# CRAFT_Negativesupply.net
KiCad netlist of a schematic drawn in Altium Designer
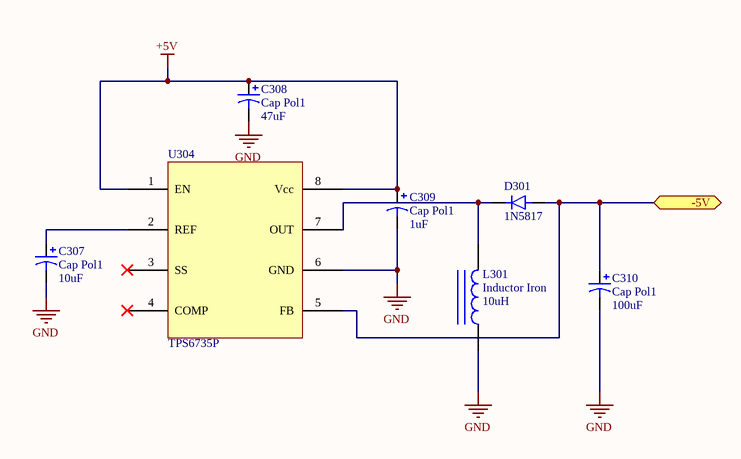
[diagram p0: CRAFT_Negativesupply.SchDoc]

(export (version "E")
  (design (tool "Eeschema 10.0.6"))
  (components
    (comp (ref "C307")
      (value "Cap Pol1")
      (footprint "CAPPRD250W50D630H1120")
      (description "Polarized Capacitor (Radial)")
      (fields (field (name "ALTIUM_VALUE") "10uF") (field (name "PUBLISHER") "Altium Limited"))
      (libsource (lib "Miscellaneous Devices") (part "Cap Pol1"))
    )
    (comp (ref "C308")
      (value "Cap Pol1")
      (footprint "CAPPRD250W50D630H1120")
      (description "Polarized Capacitor (Radial)")
      (fields (field (name "ALTIUM_VALUE") "47uF") (field (name "PUBLISHER") "Altium Limited"))
      (libsource (lib "Miscellaneous Devices") (part "Cap Pol1"))
    )
    (comp (ref "C309")
      (value "Cap Pol1")
      (footprint "CAPPRD250W50D630H1120")
      (description "Polarized Capacitor (Radial)")
      (fields (field (name "ALTIUM_VALUE") "1uF") (field (name "PUBLISHER") "Altium Limited"))
      (libsource (lib "Miscellaneous Devices") (part "Cap Pol1"))
    )
    (comp (ref "C310")
      (value "Cap Pol1")
      (footprint "CAPPRD250W50D630H1120")
      (description "Polarized Capacitor (Radial)")
      (fields (field (name "ALTIUM_VALUE") "100uF") (field (name "PUBLISHER") "Altium Limited"))
      (libsource (lib "Miscellaneous Devices") (part "Cap Pol1"))
    )
    (comp (ref "D301")
      (value "1N5817")
      (footprint "DIOAD1036W78L470D235")
      (description "Diode Schottky 20 V 1A Through Hole DO-41")
      (fields (field (name "MF") "STMicroelectronics"))
      (libsource (lib "1N5817") (part "1N5817"))
    )
    (comp (ref "L301")
      (value "Inductor Iron")
      (footprint "INDRD500W70D900H1220")
      (description "Magnetic-Core Inductor")
      (fields (field (name "ALTIUM_VALUE") "10uH") (field (name "PUBLISHER") "Altium Limited"))
      (libsource (lib "Miscellaneous Devices") (part "Inductor Iron"))
    )
    (comp (ref "U304")
      (value "TPS6735P")
      (footprint "DIP794W45P254L959H508Q8")
      (libsource (lib "CRAFTSchlib") (part "TPS6735P"))
    )
  )
  (nets
    (net (code "1") (name "+5V") (class "Default")
      (node (ref "C308") (pin "1") (pinfunction "1_1") (pintype "passive"))
      (node (ref "C309") (pin "1") (pinfunction "1_1") (pintype "passive"))
      (node (ref "U304") (pin "1") (pinfunction "EN_1") (pintype "passive"))
      (node (ref "U304") (pin "8") (pinfunction "Vcc_8") (pintype "passive"))
    )
    (net (code "2") (name "/-5V") (class "Default")
      (node (ref "C310") (pin "1") (pinfunction "1_1") (pintype "passive"))
      (node (ref "D301") (pin "A") (pinfunction "A_A") (pintype "passive"))
      (node (ref "U304") (pin "5") (pinfunction "FB_5") (pintype "passive"))
    )
    (net (code "3") (name "GND") (class "Default")
      (node (ref "C307") (pin "2") (pinfunction "2_2") (pintype "passive"))
      (node (ref "C308") (pin "2") (pinfunction "2_2") (pintype "passive"))
      (node (ref "C309") (pin "2") (pinfunction "2_2") (pintype "passive"))
      (node (ref "C310") (pin "2") (pinfunction "2_2") (pintype "passive"))
      (node (ref "L301") (pin "1") (pinfunction "1_1") (pintype "passive"))
      (node (ref "U304") (pin "6") (pinfunction "GND_6") (pintype "passive"))
    )
    (net (code "4") (name "Net-(D301-K)") (class "Default")
      (node (ref "D301") (pin "C") (pinfunction "K_C") (pintype "passive"))
      (node (ref "L301") (pin "2") (pinfunction "2_2") (pintype "passive"))
      (node (ref "U304") (pin "7") (pinfunction "OUT_7") (pintype "passive"))
    )
    (net (code "5") (name "Net-(U304-REF)") (class "Default")
      (node (ref "C307") (pin "1") (pinfunction "1_1") (pintype "passive"))
      (node (ref "U304") (pin "2") (pinfunction "REF_2") (pintype "passive"))
    )
    (net (code "6") (name "unconnected-(U304-COMP-Pad4)") (class "Default")
      (node (ref "U304") (pin "4") (pinfunction "COMP_4") (pintype "passive+no_connect"))
    )
    (net (code "7") (name "unconnected-(U304-SS-Pad3)") (class "Default")
      (node (ref "U304") (pin "3") (pinfunction "SS_3") (pintype "passive+no_connect"))
    )
  )
)
